# coreboardV0_1sch.net
KiCad netlist of a schematic drawn in Altium Designer
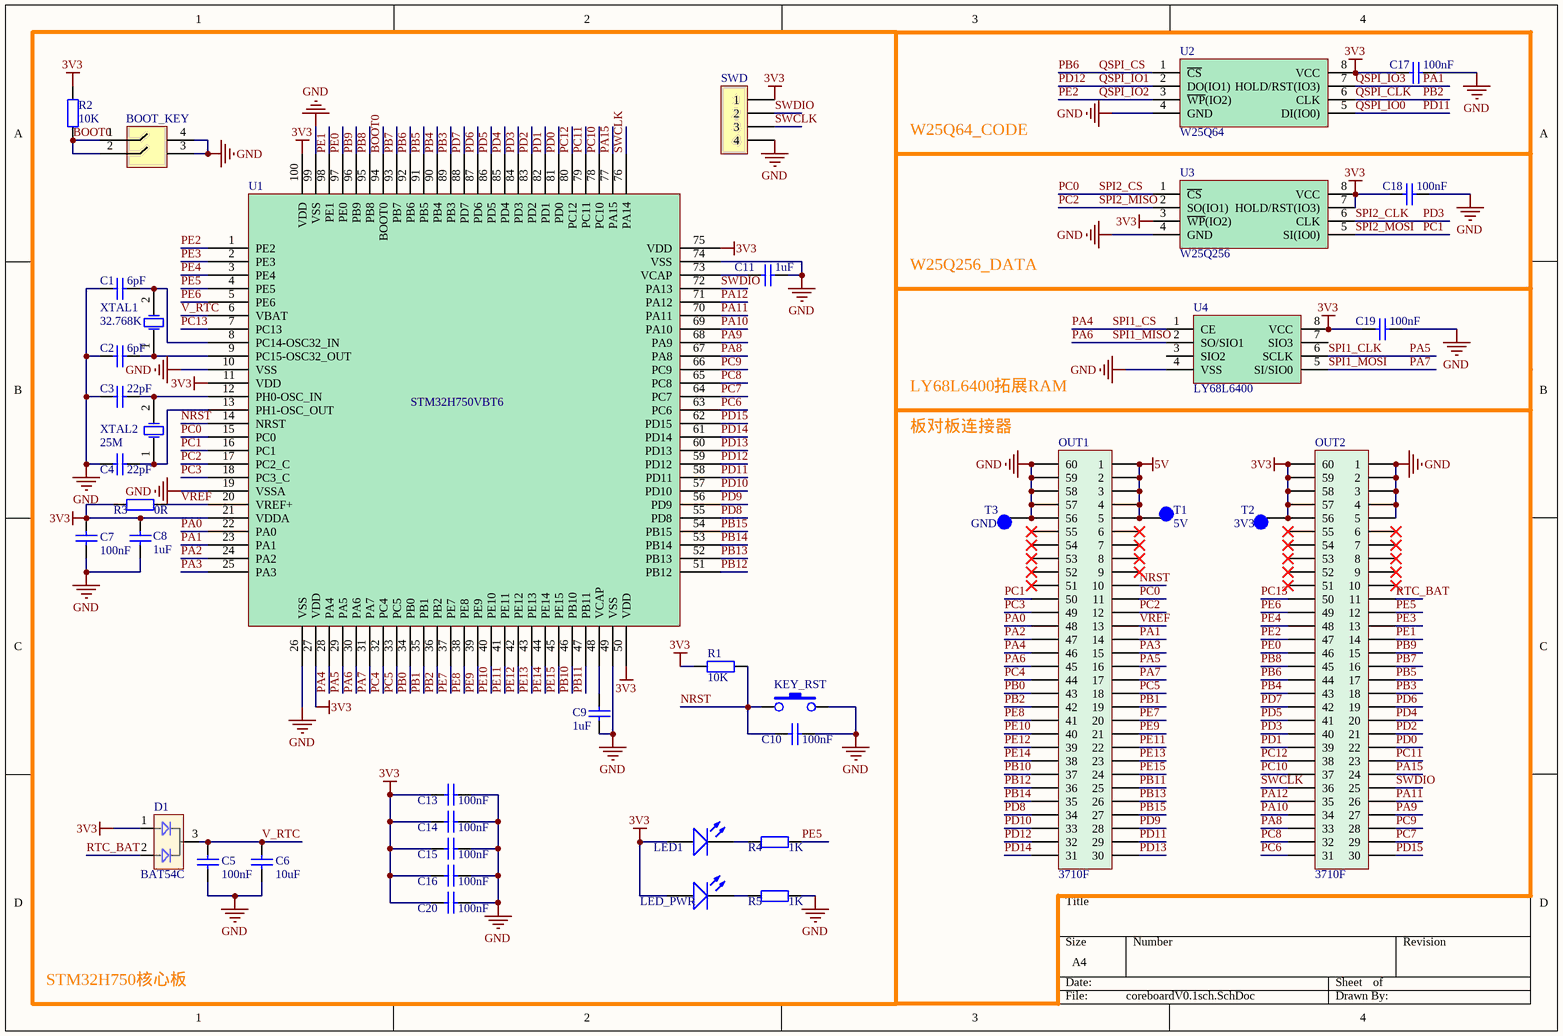
[diagram p0: coreboardV0.1sch.SchDoc]

(export (version "E")
  (design (tool "Eeschema 10.0.6"))
  (components
    (comp (ref "BOOT_KEY")
      (value "KE_2")
      (footprint "KE_2_1.27")
      (libsource (lib "MT_Device") (part "KE_2_1.27"))
    )
    (comp (ref "C1") (value "6pF") (footprint "0603_C") (libsource (lib "MT_Device") (part "0603_CAP")))
    (comp (ref "C2") (value "6pF") (footprint "0603_C") (libsource (lib "MT_Device") (part "0603_CAP")))
    (comp (ref "C3") (value "22pF") (footprint "0603_C") (libsource (lib "MT_Device") (part "0603_CAP")))
    (comp (ref "C4") (value "22pF") (footprint "0603_C") (libsource (lib "MT_Device") (part "0603_CAP")))
    (comp (ref "C5") (value "100nF") (footprint "0603_C") (libsource (lib "MT_Device") (part "0603_CAP")))
    (comp (ref "C6") (value "10uF") (footprint "0603_C") (libsource (lib "MT_Device") (part "0603_CAP")))
    (comp (ref "C7") (value "100nF") (footprint "0603_C") (libsource (lib "MT_Device") (part "0603_CAP")))
    (comp (ref "C8") (value "1uF") (footprint "0603_C") (libsource (lib "MT_Device") (part "0603_CAP")))
    (comp (ref "C9") (value "1uF") (footprint "0603_C") (libsource (lib "MT_Device") (part "0603_CAP")))
    (comp (ref "C10") (value "100nF") (footprint "0603_C") (libsource (lib "MT_Device") (part "0603_CAP")))
    (comp (ref "C11") (value "1uF") (footprint "0603_C") (libsource (lib "MT_Device") (part "0603_CAP")))
    (comp (ref "C13") (value "100nF") (footprint "0603_C") (libsource (lib "MT_Device") (part "0603_CAP")))
    (comp (ref "C14") (value "100nF") (footprint "0603_C") (libsource (lib "MT_Device") (part "0603_CAP")))
    (comp (ref "C15") (value "100nF") (footprint "0603_C") (libsource (lib "MT_Device") (part "0603_CAP")))
    (comp (ref "C16") (value "100nF") (footprint "0603_C") (libsource (lib "MT_Device") (part "0603_CAP")))
    (comp (ref "C17") (value "100nF") (footprint "0603_C") (libsource (lib "MT_Device") (part "0603_CAP")))
    (comp (ref "C18") (value "100nF") (footprint "0603_C") (libsource (lib "MT_Device") (part "0603_CAP")))
    (comp (ref "C19") (value "100nF") (footprint "0603_C") (libsource (lib "MT_Device") (part "0603_CAP")))
    (comp (ref "C20") (value "100nF") (footprint "0603_C") (libsource (lib "MT_Device") (part "0603_CAP")))
    (comp (ref "D1") (value "BAT54C") (footprint "BAT54C") (libsource (lib "MT_Device") (part "BAT54C")))
    (comp (ref "KEY_RST")
      (value "KEY_SMT")
      (footprint "KEY_SMT")
      (libsource (lib "MT_Device") (part "KEY_SMT"))
    )
    (comp (ref "LED1")
      (value "0805_LED")
      (footprint "0805_LED")
      (libsource (lib "MT_Device") (part "0805_LED"))
    )
    (comp (ref "LED_PWR")
      (value "0805_LED")
      (footprint "0805_LED")
      (libsource (lib "MT_Device") (part "0805_LED"))
    )
    (comp (ref "OUT1")
      (value "3710F")
      (footprint "3710F060046G3FT01")
      (libsource (lib "MT_Connector") (part "3710F_30*2pin"))
    )
    (comp (ref "OUT2")
      (value "3710F")
      (footprint "3710F060046G3FT01")
      (libsource (lib "MT_Connector") (part "3710F_30*2pin"))
    )
    (comp (ref "R1") (value "10K") (footprint "0603_R") (libsource (lib "") (part "0603_RES_1")))
    (comp (ref "R2") (value "10K") (footprint "0603_R") (libsource (lib "MT_Device") (part "0603_RES")))
    (comp (ref "R3") (value "0R") (footprint "0603_R") (libsource (lib "") (part "0603_RES_2")))
    (comp (ref "R4") (value "1K") (footprint "0603_R") (libsource (lib "") (part "0603_RES_2")))
    (comp (ref "R5") (value "1K") (footprint "0603_R") (libsource (lib "") (part "0603_RES_2")))
    (comp (ref "SWD")
      (value "Header_2.54_4P")
      (footprint "HDR1_4P")
      (libsource (lib "MT_Connector") (part "Header_2.54_4P"))
    )
    (comp (ref "T1")
      (value "5V")
      (footprint "TEST_POINT_2mm")
      (libsource (lib "MT_Connector") (part "TEST_POINT_2mm"))
    )
    (comp (ref "T2")
      (value "3V3")
      (footprint "TEST_POINT_2mm")
      (libsource (lib "MT_Connector") (part "TEST_POINT_2mm"))
    )
    (comp (ref "T3")
      (value "GND")
      (footprint "TEST_POINT_2mm")
      (libsource (lib "MT_Connector") (part "TEST_POINT_2mm"))
    )
    (comp (ref "U1")
      (value "STM32H750VBT6")
      (footprint "LQFP100")
      (libsource (lib "MT_Chip") (part "STM32H750VBT6"))
    )
    (comp (ref "U2") (value "W25Q64") (footprint "SOIC8-208MIL") (libsource (lib "MT_Chip") (part "W25Q64")))
    (comp (ref "U3") (value "W25Q256") (footprint "WSON8") (libsource (lib "MT_Chip") (part "W25Q256")))
    (comp (ref "U4")
      (value "LY68L6400")
      (footprint "SOP8-150MIL")
      (libsource (lib "MT_Chip") (part "LY68L6400"))
    )
    (comp (ref "XTAL1")
      (value "32.768K")
      (footprint "XTAL_32.768_3215_2")
      (libsource (lib "MT_Device") (part "XTAL_32.768_3215_2"))
    )
    (comp (ref "XTAL2")
      (value "25M")
      (footprint "XTAL_5032_2")
      (libsource (lib "MT_Device") (part "XTAL_8MHz_5032_2"))
    )
  )
  (nets
    (net (code "1") (name "/BOOT0") (class "Default")
      (node (ref "BOOT_KEY") (pin "1") (pinfunction "1_1") (pintype "passive"))
      (node (ref "BOOT_KEY") (pin "2") (pinfunction "2_2") (pintype "passive"))
      (node (ref "R2") (pin "2") (pinfunction "2_2") (pintype "passive"))
      (node (ref "U1") (pin "94") (pinfunction "BOOT0_94") (pintype "passive"))
    )
    (net (code "2") (name "/NRST") (class "Default")
      (node (ref "C10") (pin "2") (pinfunction "2_2") (pintype "passive"))
      (node (ref "KEY_RST") (pin "1") (pinfunction "1_1") (pintype "passive"))
      (node (ref "OUT1") (pin "10") (pinfunction "10_10") (pintype "passive"))
      (node (ref "R1") (pin "1") (pinfunction "1_1") (pintype "passive"))
      (node (ref "U1") (pin "14") (pinfunction "NRST_14") (pintype "passive"))
    )
    (net (code "3") (name "/PA0") (class "Default")
      (node (ref "OUT1") (pin "48") (pinfunction "48_48") (pintype "passive"))
      (node (ref "U1") (pin "22") (pinfunction "PA0_22") (pintype "passive"))
    )
    (net (code "4") (name "/PA1") (class "Default")
      (node (ref "OUT1") (pin "14") (pinfunction "14_14") (pintype "passive"))
      (node (ref "U1") (pin "23") (pinfunction "PA1_23") (pintype "passive"))
      (node (ref "U2") (pin "7") (pinfunction "HOLD/RST(IO3)_7") (pintype "power_in"))
    )
    (net (code "5") (name "/PA2") (class "Default")
      (node (ref "OUT1") (pin "47") (pinfunction "47_47") (pintype "passive"))
      (node (ref "U1") (pin "24") (pinfunction "PA2_24") (pintype "passive"))
    )
    (net (code "6") (name "/PA3") (class "Default")
      (node (ref "OUT1") (pin "15") (pinfunction "15_15") (pintype "passive"))
      (node (ref "U1") (pin "25") (pinfunction "PA3_25") (pintype "passive"))
    )
    (net (code "7") (name "/PA4") (class "Default")
      (node (ref "OUT1") (pin "46") (pinfunction "46_46") (pintype "passive"))
      (node (ref "U1") (pin "28") (pinfunction "PA4_28") (pintype "passive"))
      (node (ref "U4") (pin "1") (pinfunction "CE_1") (pintype "passive"))
    )
    (net (code "8") (name "/PA5") (class "Default")
      (node (ref "OUT1") (pin "16") (pinfunction "16_16") (pintype "passive"))
      (node (ref "U1") (pin "29") (pinfunction "PA5_29") (pintype "passive"))
      (node (ref "U4") (pin "6") (pinfunction "SCLK_6") (pintype "passive"))
    )
    (net (code "9") (name "/PA6") (class "Default")
      (node (ref "OUT1") (pin "45") (pinfunction "45_45") (pintype "passive"))
      (node (ref "U1") (pin "30") (pinfunction "PA6_30") (pintype "passive"))
      (node (ref "U4") (pin "2") (pinfunction "SO/SIO1_2") (pintype "passive"))
    )
    (net (code "10") (name "/PA7") (class "Default")
      (node (ref "OUT1") (pin "17") (pinfunction "17_17") (pintype "passive"))
      (node (ref "U1") (pin "31") (pinfunction "PA7_31") (pintype "passive"))
      (node (ref "U4") (pin "5") (pinfunction "SI/SIO0_5") (pintype "passive"))
    )
    (net (code "11") (name "/PA8") (class "Default")
      (node (ref "OUT2") (pin "33") (pinfunction "33_33") (pintype "passive"))
      (node (ref "U1") (pin "67") (pinfunction "PA8_67") (pintype "passive"))
    )
    (net (code "12") (name "/PA9") (class "Default")
      (node (ref "OUT2") (pin "27") (pinfunction "27_27") (pintype "passive"))
      (node (ref "U1") (pin "68") (pinfunction "PA9_68") (pintype "passive"))
    )
    (net (code "13") (name "/PA10") (class "Default")
      (node (ref "OUT2") (pin "34") (pinfunction "34_34") (pintype "passive"))
      (node (ref "U1") (pin "69") (pinfunction "PA10_69") (pintype "passive"))
    )
    (net (code "14") (name "/PA11") (class "Default")
      (node (ref "OUT2") (pin "26") (pinfunction "26_26") (pintype "passive"))
      (node (ref "U1") (pin "70") (pinfunction "PA11_70") (pintype "passive"))
    )
    (net (code "15") (name "/PA12") (class "Default")
      (node (ref "OUT2") (pin "35") (pinfunction "35_35") (pintype "passive"))
      (node (ref "U1") (pin "71") (pinfunction "PA12_71") (pintype "passive"))
    )
    (net (code "16") (name "/PA15") (class "Default")
      (node (ref "OUT2") (pin "24") (pinfunction "24_24") (pintype "passive"))
      (node (ref "U1") (pin "77") (pinfunction "PA15_77") (pintype "passive"))
    )
    (net (code "17") (name "/PB0") (class "Default")
      (node (ref "OUT1") (pin "43") (pinfunction "43_43") (pintype "passive"))
      (node (ref "U1") (pin "34") (pinfunction "PB0_34") (pintype "passive"))
    )
    (net (code "18") (name "/PB1") (class "Default")
      (node (ref "OUT1") (pin "19") (pinfunction "19_19") (pintype "passive"))
      (node (ref "U1") (pin "35") (pinfunction "PB1_35") (pintype "passive"))
    )
    (net (code "19") (name "/PB2") (class "Default")
      (node (ref "OUT1") (pin "42") (pinfunction "42_42") (pintype "passive"))
      (node (ref "U1") (pin "36") (pinfunction "PB2_36") (pintype "passive"))
      (node (ref "U2") (pin "6") (pinfunction "CLK_6") (pintype "passive"))
    )
    (net (code "20") (name "/PB3") (class "Default")
      (node (ref "OUT2") (pin "18") (pinfunction "18_18") (pintype "passive"))
      (node (ref "U1") (pin "89") (pinfunction "PB3_89") (pintype "passive"))
    )
    (net (code "21") (name "/PB4") (class "Default")
      (node (ref "OUT2") (pin "43") (pinfunction "43_43") (pintype "passive"))
      (node (ref "U1") (pin "90") (pinfunction "PB4_90") (pintype "passive"))
    )
    (net (code "22") (name "/PB5") (class "Default")
      (node (ref "OUT2") (pin "17") (pinfunction "17_17") (pintype "passive"))
      (node (ref "U1") (pin "91") (pinfunction "PB5_91") (pintype "passive"))
    )
    (net (code "23") (name "/PB6") (class "Default")
      (node (ref "OUT2") (pin "44") (pinfunction "44_44") (pintype "passive"))
      (node (ref "U1") (pin "92") (pinfunction "PB6_92") (pintype "passive"))
      (node (ref "U2") (pin "1") (pinfunction "~{CS}_1") (pintype "passive"))
    )
    (net (code "24") (name "/PB7") (class "Default")
      (node (ref "OUT2") (pin "16") (pinfunction "16_16") (pintype "passive"))
      (node (ref "U1") (pin "93") (pinfunction "PB7_93") (pintype "passive"))
    )
    (net (code "25") (name "/PB8") (class "Default")
      (node (ref "OUT2") (pin "45") (pinfunction "45_45") (pintype "passive"))
      (node (ref "U1") (pin "95") (pinfunction "PB8_95") (pintype "passive"))
    )
    (net (code "26") (name "/PB9") (class "Default")
      (node (ref "OUT2") (pin "15") (pinfunction "15_15") (pintype "passive"))
      (node (ref "U1") (pin "96") (pinfunction "PB9_96") (pintype "passive"))
    )
    (net (code "27") (name "/PB10") (class "Default")
      (node (ref "OUT1") (pin "37") (pinfunction "37_37") (pintype "passive"))
      (node (ref "U1") (pin "46") (pinfunction "PB10_46") (pintype "passive"))
    )
    (net (code "28") (name "/PB11") (class "Default")
      (node (ref "OUT1") (pin "25") (pinfunction "25_25") (pintype "passive"))
      (node (ref "U1") (pin "47") (pinfunction "PB11_47") (pintype "passive"))
    )
    (net (code "29") (name "/PB12") (class "Default")
      (node (ref "OUT1") (pin "36") (pinfunction "36_36") (pintype "passive"))
      (node (ref "U1") (pin "51") (pinfunction "PB12_51") (pintype "passive"))
    )
    (net (code "30") (name "/PB13") (class "Default")
      (node (ref "OUT1") (pin "26") (pinfunction "26_26") (pintype "passive"))
      (node (ref "U1") (pin "52") (pinfunction "PB13_52") (pintype "passive"))
    )
    (net (code "31") (name "/PB14") (class "Default")
      (node (ref "OUT1") (pin "35") (pinfunction "35_35") (pintype "passive"))
      (node (ref "U1") (pin "53") (pinfunction "PB14_53") (pintype "passive"))
    )
    (net (code "32") (name "/PB15") (class "Default")
      (node (ref "OUT1") (pin "27") (pinfunction "27_27") (pintype "passive"))
      (node (ref "U1") (pin "54") (pinfunction "PB15_54") (pintype "passive"))
    )
    (net (code "33") (name "/PC0") (class "Default")
      (node (ref "OUT1") (pin "11") (pinfunction "11_11") (pintype "passive"))
      (node (ref "U1") (pin "15") (pinfunction "PC0_15") (pintype "passive"))
      (node (ref "U3") (pin "1") (pinfunction "~{CS}_1") (pintype "passive"))
    )
    (net (code "34") (name "/PC1") (class "Default")
      (node (ref "OUT1") (pin "50") (pinfunction "50_50") (pintype "passive"))
      (node (ref "U1") (pin "16") (pinfunction "PC1_16") (pintype "passive"))
      (node (ref "U3") (pin "5") (pinfunction "SI(IO0)_5") (pintype "power_in"))
    )
    (net (code "35") (name "/PC2") (class "Default")
      (node (ref "OUT1") (pin "12") (pinfunction "12_12") (pintype "passive"))
      (node (ref "U1") (pin "17") (pinfunction "PC2_C_17") (pintype "passive"))
      (node (ref "U3") (pin "2") (pinfunction "SO(IO1)_2") (pintype "passive"))
    )
    (net (code "36") (name "/PC3") (class "Default")
      (node (ref "OUT1") (pin "49") (pinfunction "49_49") (pintype "passive"))
      (node (ref "U1") (pin "18") (pinfunction "PC3_C_18") (pintype "passive"))
    )
    (net (code "37") (name "/PC4") (class "Default")
      (node (ref "OUT1") (pin "44") (pinfunction "44_44") (pintype "passive"))
      (node (ref "U1") (pin "32") (pinfunction "PC4_32") (pintype "passive"))
    )
    (net (code "38") (name "/PC5") (class "Default")
      (node (ref "OUT1") (pin "18") (pinfunction "18_18") (pintype "passive"))
      (node (ref "U1") (pin "33") (pinfunction "PC5_33") (pintype "passive"))
    )
    (net (code "39") (name "/PC6") (class "Default")
      (node (ref "OUT2") (pin "31") (pinfunction "31_31") (pintype "passive"))
      (node (ref "U1") (pin "63") (pinfunction "PC6_63") (pintype "passive"))
    )
    (net (code "40") (name "/PC7") (class "Default")
      (node (ref "OUT2") (pin "29") (pinfunction "29_29") (pintype "passive"))
      (node (ref "U1") (pin "64") (pinfunction "PC7_64") (pintype "passive"))
    )
    (net (code "41") (name "/PC8") (class "Default")
      (node (ref "OUT2") (pin "32") (pinfunction "32_32") (pintype "passive"))
      (node (ref "U1") (pin "65") (pinfunction "PC8_65") (pintype "passive"))
    )
    (net (code "42") (name "/PC9") (class "Default")
      (node (ref "OUT2") (pin "28") (pinfunction "28_28") (pintype "passive"))
      (node (ref "U1") (pin "66") (pinfunction "PC9_66") (pintype "passive"))
    )
    (net (code "43") (name "/PC10") (class "Default")
      (node (ref "OUT2") (pin "37") (pinfunction "37_37") (pintype "passive"))
      (node (ref "U1") (pin "78") (pinfunction "PC10_78") (pintype "passive"))
    )
    (net (code "44") (name "/PC11") (class "Default")
      (node (ref "OUT2") (pin "23") (pinfunction "23_23") (pintype "passive"))
      (node (ref "U1") (pin "79") (pinfunction "PC11_79") (pintype "passive"))
    )
    (net (code "45") (name "/PC12") (class "Default")
      (node (ref "OUT2") (pin "38") (pinfunction "38_38") (pintype "passive"))
      (node (ref "U1") (pin "80") (pinfunction "PC12_80") (pintype "passive"))
    )
    (net (code "46") (name "/PC13") (class "Default")
      (node (ref "OUT2") (pin "50") (pinfunction "50_50") (pintype "passive"))
      (node (ref "U1") (pin "7") (pinfunction "PC13_7") (pintype "passive"))
    )
    (net (code "47") (name "/PD0") (class "Default")
      (node (ref "OUT2") (pin "22") (pinfunction "22_22") (pintype "passive"))
      (node (ref "U1") (pin "81") (pinfunction "PD0_81") (pintype "passive"))
    )
    (net (code "48") (name "/PD1") (class "Default")
      (node (ref "OUT2") (pin "39") (pinfunction "39_39") (pintype "passive"))
      (node (ref "U1") (pin "82") (pinfunction "PD1_82") (pintype "passive"))
    )
    (net (code "49") (name "/PD2") (class "Default")
      (node (ref "OUT2") (pin "21") (pinfunction "21_21") (pintype "passive"))
      (node (ref "U1") (pin "83") (pinfunction "PD2_83") (pintype "passive"))
    )
    (net (code "50") (name "/PD3") (class "Default")
      (node (ref "OUT2") (pin "40") (pinfunction "40_40") (pintype "passive"))
      (node (ref "U1") (pin "84") (pinfunction "PD3_84") (pintype "passive"))
      (node (ref "U3") (pin "6") (pinfunction "CLK_6") (pintype "passive"))
    )
    (net (code "51") (name "/PD4") (class "Default")
      (node (ref "OUT2") (pin "20") (pinfunction "20_20") (pintype "passive"))
      (node (ref "U1") (pin "85") (pinfunction "PD4_85") (pintype "passive"))
    )
    (net (code "52") (name "/PD5") (class "Default")
      (node (ref "OUT2") (pin "41") (pinfunction "41_41") (pintype "passive"))
      (node (ref "U1") (pin "86") (pinfunction "PD5_86") (pintype "passive"))
    )
    (net (code "53") (name "/PD6") (class "Default")
      (node (ref "OUT2") (pin "19") (pinfunction "19_19") (pintype "passive"))
      (node (ref "U1") (pin "87") (pinfunction "PD6_87") (pintype "passive"))
    )
    (net (code "54") (name "/PD7") (class "Default")
      (node (ref "OUT2") (pin "42") (pinfunction "42_42") (pintype "passive"))
      (node (ref "U1") (pin "88") (pinfunction "PD7_88") (pintype "passive"))
    )
    (net (code "55") (name "/PD8") (class "Default")
      (node (ref "OUT1") (pin "34") (pinfunction "34_34") (pintype "passive"))
      (node (ref "U1") (pin "55") (pinfunction "PD8_55") (pintype "passive"))
    )
    (net (code "56") (name "/PD9") (class "Default")
      (node (ref "OUT1") (pin "28") (pinfunction "28_28") (pintype "passive"))
      (node (ref "U1") (pin "56") (pinfunction "PD9_56") (pintype "passive"))
    )
    (net (code "57") (name "/PD10") (class "Default")
      (node (ref "OUT1") (pin "33") (pinfunction "33_33") (pintype "passive"))
      (node (ref "U1") (pin "57") (pinfunction "PD10_57") (pintype "passive"))
    )
    (net (code "58") (name "/PD11") (class "Default")
      (node (ref "OUT1") (pin "29") (pinfunction "29_29") (pintype "passive"))
      (node (ref "U1") (pin "58") (pinfunction "PD11_58") (pintype "passive"))
      (node (ref "U2") (pin "5") (pinfunction "DI(IO0)_5") (pintype "power_in"))
    )
    (net (code "59") (name "/PD12") (class "Default")
      (node (ref "OUT1") (pin "32") (pinfunction "32_32") (pintype "passive"))
      (node (ref "U1") (pin "59") (pinfunction "PD12_59") (pintype "passive"))
      (node (ref "U2") (pin "2") (pinfunction "DO(IO1)_2") (pintype "passive"))
    )
    (net (code "60") (name "/PD13") (class "Default")
      (node (ref "OUT1") (pin "30") (pinfunction "30_30") (pintype "passive"))
      (node (ref "U1") (pin "60") (pinfunction "PD13_60") (pintype "passive"))
    )
    (net (code "61") (name "/PD14") (class "Default")
      (node (ref "OUT1") (pin "31") (pinfunction "31_31") (pintype "passive"))
      (node (ref "U1") (pin "61") (pinfunction "PD14_61") (pintype "passive"))
    )
    (net (code "62") (name "/PD15") (class "Default")
      (node (ref "OUT2") (pin "30") (pinfunction "30_30") (pintype "passive"))
      (node (ref "U1") (pin "62") (pinfunction "PD15_62") (pintype "passive"))
    )
    (net (code "63") (name "/PE0") (class "Default")
      (node (ref "OUT2") (pin "46") (pinfunction "46_46") (pintype "passive"))
      (node (ref "U1") (pin "97") (pinfunction "PE0_97") (pintype "passive"))
    )
    (net (code "64") (name "/PE1") (class "Default")
      (node (ref "OUT2") (pin "14") (pinfunction "14_14") (pintype "passive"))
      (node (ref "U1") (pin "98") (pinfunction "PE1_98") (pintype "passive"))
    )
    (net (code "65") (name "/PE2") (class "Default")
      (node (ref "OUT2") (pin "47") (pinfunction "47_47") (pintype "passive"))
      (node (ref "U1") (pin "1") (pinfunction "PE2_1") (pintype "passive"))
      (node (ref "U2") (pin "3") (pinfunction "~{WP}(IO2)_3") (pintype "passive"))
    )
    (net (code "66") (name "/PE3") (class "Default")
      (node (ref "OUT2") (pin "13") (pinfunction "13_13") (pintype "passive"))
      (node (ref "U1") (pin "2") (pinfunction "PE3_2") (pintype "passive"))
    )
    (net (code "67") (name "/PE4") (class "Default")
      (node (ref "OUT2") (pin "48") (pinfunction "48_48") (pintype "passive"))
      (node (ref "U1") (pin "3") (pinfunction "PE4_3") (pintype "passive"))
    )
    (net (code "68") (name "/PE5") (class "Default")
      (node (ref "OUT2") (pin "12") (pinfunction "12_12") (pintype "passive"))
      (node (ref "R4") (pin "2") (pinfunction "2_2") (pintype "passive"))
      (node (ref "U1") (pin "4") (pinfunction "PE5_4") (pintype "passive"))
    )
    (net (code "69") (name "/PE6") (class "Default")
      (node (ref "OUT2") (pin "49") (pinfunction "49_49") (pintype "passive"))
      (node (ref "U1") (pin "5") (pinfunction "PE6_5") (pintype "passive"))
    )
    (net (code "70") (name "/PE7") (class "Default")
      (node (ref "OUT1") (pin "20") (pinfunction "20_20") (pintype "passive"))
      (node (ref "U1") (pin "37") (pinfunction "PE7_37") (pintype "passive"))
    )
    (net (code "71") (name "/PE8") (class "Default")
      (node (ref "OUT1") (pin "41") (pinfunction "41_41") (pintype "passive"))
      (node (ref "U1") (pin "38") (pinfunction "PE8_38") (pintype "passive"))
    )
    (net (code "72") (name "/PE9") (class "Default")
      (node (ref "OUT1") (pin "21") (pinfunction "21_21") (pintype "passive"))
      (node (ref "U1") (pin "39") (pinfunction "PE9_39") (pintype "passive"))
    )
    (net (code "73") (name "/PE10") (class "Default")
      (node (ref "OUT1") (pin "40") (pinfunction "40_40") (pintype "passive"))
      (node (ref "U1") (pin "40") (pinfunction "PE10_40") (pintype "passive"))
    )
    (net (code "74") (name "/PE11") (class "Default")
      (node (ref "OUT1") (pin "22") (pinfunction "22_22") (pintype "passive"))
      (node (ref "U1") (pin "41") (pinfunction "PE11_41") (pintype "passive"))
    )
    (net (code "75") (name "/PE12") (class "Default")
      (node (ref "OUT1") (pin "39") (pinfunction "39_39") (pintype "passive"))
      (node (ref "U1") (pin "42") (pinfunction "PE12_42") (pintype "passive"))
    )
    (net (code "76") (name "/PE13") (class "Default")
      (node (ref "OUT1") (pin "23") (pinfunction "23_23") (pintype "passive"))
      (node (ref "U1") (pin "43") (pinfunction "PE13_43") (pintype "passive"))
    )
    (net (code "77") (name "/PE14") (class "Default")
      (node (ref "OUT1") (pin "38") (pinfunction "38_38") (pintype "passive"))
      (node (ref "U1") (pin "44") (pinfunction "PE14_44") (pintype "passive"))
    )
    (net (code "78") (name "/PE15") (class "Default")
      (node (ref "OUT1") (pin "24") (pinfunction "24_24") (pintype "passive"))
      (node (ref "U1") (pin "45") (pinfunction "PE15_45") (pintype "passive"))
    )
    (net (code "79") (name "/RTC_BAT") (class "Default")
      (node (ref "D1") (pin "2") (pinfunction "2_2") (pintype "passive"))
      (node (ref "OUT2") (pin "11") (pinfunction "11_11") (pintype "passive"))
    )
    (net (code "80") (name "/SWCLK") (class "Default")
      (node (ref "OUT2") (pin "36") (pinfunction "36_36") (pintype "passive"))
      (node (ref "SWD") (pin "3") (pinfunction "3_3") (pintype "passive"))
      (node (ref "U1") (pin "76") (pinfunction "PA14_76") (pintype "passive"))
    )
    (net (code "81") (name "/SWDIO") (class "Default")
      (node (ref "OUT2") (pin "25") (pinfunction "25_25") (pintype "passive"))
      (node (ref "SWD") (pin "2") (pinfunction "2_2") (pintype "passive"))
      (node (ref "U1") (pin "72") (pinfunction "PA13_72") (pintype "passive"))
    )
    (net (code "82") (name "/VREF") (class "Default")
      (node (ref "OUT1") (pin "13") (pinfunction "13_13") (pintype "passive"))
      (node (ref "R3") (pin "2") (pinfunction "2_2") (pintype "passive"))
      (node (ref "U1") (pin "20") (pinfunction "VREF+_20") (pintype "passive"))
    )
    (net (code "83") (name "/V_RTC") (class "Default")
      (node (ref "C5") (pin "2") (pinfunction "2_2") (pintype "passive"))
      (node (ref "C6") (pin "2") (pinfunction "2_2") (pintype "passive"))
      (node (ref "D1") (pin "3") (pinfunction "3_3") (pintype "passive"))
      (node (ref "U1") (pin "6") (pinfunction "VBAT_6") (pintype "passive"))
    )
    (net (code "84") (name "3V3") (class "Default")
      (node (ref "C13") (pin "2") (pinfunction "2_2") (pintype "passive"))
      (node (ref "C14") (pin "2") (pinfunction "2_2") (pintype "passive"))
      (node (ref "C15") (pin "2") (pinfunction "2_2") (pintype "passive"))
      (node (ref "C16") (pin "2") (pinfunction "2_2") (pintype "passive"))
      (node (ref "C17") (pin "1") (pinfunction "1_1") (pintype "passive"))
      (node (ref "C18") (pin "1") (pinfunction "1_1") (pintype "passive"))
      (node (ref "C19") (pin "1") (pinfunction "1_1") (pintype "passive"))
      (node (ref "C20") (pin "2") (pinfunction "2_2") (pintype "passive"))
      (node (ref "C7") (pin "2") (pinfunction "2_2") (pintype "passive"))
      (node (ref "C8") (pin "1") (pinfunction "1_1") (pintype "passive"))
      (node (ref "D1") (pin "1") (pinfunction "1_1") (pintype "passive"))
      (node (ref "LED1") (pin "A") (pinfunction "A_A") (pintype "passive"))
      (node (ref "LED_PWR") (pin "A") (pinfunction "A_A") (pintype "passive"))
      (node (ref "OUT2") (pin "56") (pinfunction "56_56") (pintype "passive"))
      (node (ref "OUT2") (pin "57") (pinfunction "57_57") (pintype "passive"))
      (node (ref "OUT2") (pin "58") (pinfunction "58_58") (pintype "passive"))
      (node (ref "OUT2") (pin "59") (pinfunction "59_59") (pintype "passive"))
      (node (ref "OUT2") (pin "60") (pinfunction "60_60") (pintype "passive"))
      (node (ref "R1") (pin "2") (pinfunction "2_2") (pintype "passive"))
      (node (ref "R2") (pin "1") (pinfunction "1_1") (pintype "passive"))
      (node (ref "R3") (pin "1") (pinfunction "1_1") (pintype "passive"))
      (node (ref "SWD") (pin "1") (pinfunction "1_1") (pintype "passive"))
      (node (ref "T2") (pin "1") (pinfunction "1_1") (pintype "passive"))
      (node (ref "U1") (pin "100") (pinfunction "VDD_100") (pintype "passive"))
      (node (ref "U1") (pin "11") (pinfunction "VDD_11") (pintype "passive"))
      (node (ref "U1") (pin "21") (pinfunction "VDDA_21") (pintype "passive"))
      (node (ref "U1") (pin "27") (pinfunction "VDD_27") (pintype "passive"))
      (node (ref "U1") (pin "50") (pinfunction "VDD_50") (pintype "passive"))
      (node (ref "U1") (pin "75") (pinfunction "VDD_75") (pintype "passive"))
      (node (ref "U2") (pin "8") (pinfunction "VCC_8") (pintype "passive"))
      (node (ref "U3") (pin "3") (pinfunction "~{WP}(IO2)_3") (pintype "passive"))
      (node (ref "U3") (pin "7") (pinfunction "HOLD/RST(IO3)_7") (pintype "power_in"))
      (node (ref "U3") (pin "8") (pinfunction "VCC_8") (pintype "passive"))
      (node (ref "U4") (pin "8") (pinfunction "VCC_8") (pintype "passive"))
    )
    (net (code "85") (name "5V") (class "Default")
      (node (ref "OUT1") (pin "1") (pinfunction "1_1") (pintype "passive"))
      (node (ref "OUT1") (pin "2") (pinfunction "2_2") (pintype "passive"))
      (node (ref "OUT1") (pin "3") (pinfunction "3_3") (pintype "passive"))
      (node (ref "OUT1") (pin "4") (pinfunction "4_4") (pintype "passive"))
      (node (ref "OUT1") (pin "5") (pinfunction "5_5") (pintype "passive"))
      (node (ref "T1") (pin "1") (pinfunction "1_1") (pintype "passive"))
    )
    (net (code "86") (name "GND") (class "Default")
      (node (ref "BOOT_KEY") (pin "3") (pinfunction "3_3") (pintype "passive"))
      (node (ref "BOOT_KEY") (pin "4") (pinfunction "4_4") (pintype "passive"))
      (node (ref "C1") (pin "1") (pinfunction "1_1") (pintype "passive"))
      (node (ref "C10") (pin "1") (pinfunction "1_1") (pintype "passive"))
      (node (ref "C11") (pin "2") (pinfunction "2_2") (pintype "passive"))
      (node (ref "C13") (pin "1") (pinfunction "1_1") (pintype "passive"))
      (node (ref "C14") (pin "1") (pinfunction "1_1") (pintype "passive"))
      (node (ref "C15") (pin "1") (pinfunction "1_1") (pintype "passive"))
      (node (ref "C16") (pin "1") (pinfunction "1_1") (pintype "passive"))
      (node (ref "C17") (pin "2") (pinfunction "2_2") (pintype "passive"))
      (node (ref "C18") (pin "2") (pinfunction "2_2") (pintype "passive"))
      (node (ref "C19") (pin "2") (pinfunction "2_2") (pintype "passive"))
      (node (ref "C2") (pin "1") (pinfunction "1_1") (pintype "passive"))
      (node (ref "C20") (pin "1") (pinfunction "1_1") (pintype "passive"))
      (node (ref "C3") (pin "1") (pinfunction "1_1") (pintype "passive"))
      (node (ref "C4") (pin "1") (pinfunction "1_1") (pintype "passive"))
      (node (ref "C5") (pin "1") (pinfunction "1_1") (pintype "passive"))
      (node (ref "C6") (pin "1") (pinfunction "1_1") (pintype "passive"))
      (node (ref "C7") (pin "1") (pinfunction "1_1") (pintype "passive"))
      (node (ref "C8") (pin "2") (pinfunction "2_2") (pintype "passive"))
      (node (ref "C9") (pin "2") (pinfunction "2_2") (pintype "passive"))
      (node (ref "KEY_RST") (pin "2") (pinfunction "2_2") (pintype "passive"))
      (node (ref "OUT1") (pin "56") (pinfunction "56_56") (pintype "passive"))
      (node (ref "OUT1") (pin "57") (pinfunction "57_57") (pintype "passive"))
      (node (ref "OUT1") (pin "58") (pinfunction "58_58") (pintype "passive"))
      (node (ref "OUT1") (pin "59") (pinfunction "59_59") (pintype "passive"))
      (node (ref "OUT1") (pin "60") (pinfunction "60_60") (pintype "passive"))
      (node (ref "OUT2") (pin "1") (pinfunction "1_1") (pintype "passive"))
      (node (ref "OUT2") (pin "2") (pinfunction "2_2") (pintype "passive"))
      (node (ref "OUT2") (pin "3") (pinfunction "3_3") (pintype "passive"))
      (node (ref "OUT2") (pin "4") (pinfunction "4_4") (pintype "passive"))
      (node (ref "OUT2") (pin "5") (pinfunction "5_5") (pintype "passive"))
      (node (ref "R5") (pin "2") (pinfunction "2_2") (pintype "passive"))
      (node (ref "SWD") (pin "4") (pinfunction "4_4") (pintype "passive"))
      (node (ref "T3") (pin "1") (pinfunction "1_1") (pintype "passive"))
      (node (ref "U1") (pin "10") (pinfunction "VSS_10") (pintype "passive"))
      (node (ref "U1") (pin "19") (pinfunction "VSSA_19") (pintype "passive"))
      (node (ref "U1") (pin "26") (pinfunction "VSS_26") (pintype "passive"))
      (node (ref "U1") (pin "49") (pinfunction "VSS_49") (pintype "passive"))
      (node (ref "U1") (pin "74") (pinfunction "VSS_74") (pintype "passive"))
      (node (ref "U1") (pin "99") (pinfunction "VSS_99") (pintype "passive"))
      (node (ref "U2") (pin "4") (pinfunction "GND_4") (pintype "passive"))
      (node (ref "U3") (pin "4") (pinfunction "GND_4") (pintype "passive"))
      (node (ref "U4") (pin "4") (pinfunction "VSS_4") (pintype "passive"))
    )
    (net (code "87") (name "Net-(C9-Pad1)") (class "Default")
      (node (ref "C9") (pin "1") (pinfunction "1_1") (pintype "passive"))
      (node (ref "U1") (pin "48") (pinfunction "VCAP_48") (pintype "passive"))
    )
    (net (code "88") (name "Net-(C11-Pad1)") (class "Default")
      (node (ref "C11") (pin "1") (pinfunction "1_1") (pintype "passive"))
      (node (ref "U1") (pin "73") (pinfunction "VCAP_73") (pintype "passive"))
    )
    (net (code "89") (name "Net-(LED1-PadK)") (class "Default")
      (node (ref "LED1") (pin "K") (pinfunction "K_K") (pintype "passive"))
      (node (ref "R4") (pin "1") (pinfunction "1_1") (pintype "passive"))
    )
    (net (code "90") (name "Net-(LED_PWR-PadK)") (class "Default")
      (node (ref "LED_PWR") (pin "K") (pinfunction "K_K") (pintype "passive"))
      (node (ref "R5") (pin "1") (pinfunction "1_1") (pintype "passive"))
    )
    (net (code "91") (name "Net-(U1-PC14-OSC32_IN)") (class "Default")
      (node (ref "C1") (pin "2") (pinfunction "2_2") (pintype "passive"))
      (node (ref "U1") (pin "8") (pinfunction "PC14-OSC32_IN_8") (pintype "passive"))
      (node (ref "XTAL1") (pin "2") (pinfunction "OSC2_2") (pintype "passive"))
    )
    (net (code "92") (name "Net-(U1-PC15-OSC32_OUT)") (class "Default")
      (node (ref "C2") (pin "2") (pinfunction "2_2") (pintype "passive"))
      (node (ref "U1") (pin "9") (pinfunction "PC15-OSC32_OUT_9") (pintype "passive"))
      (node (ref "XTAL1") (pin "1") (pinfunction "OSC1_1") (pintype "passive"))
    )
    (net (code "93") (name "Net-(U1-PH0-OSC_IN)") (class "Default")
      (node (ref "C3") (pin "2") (pinfunction "2_2") (pintype "passive"))
      (node (ref "U1") (pin "12") (pinfunction "PH0-OSC_IN_12") (pintype "passive"))
      (node (ref "XTAL2") (pin "2") (pinfunction "OSC2_2") (pintype "passive"))
    )
    (net (code "94") (name "Net-(U1-PH1-OSC_OUT)") (class "Default")
      (node (ref "C4") (pin "2") (pinfunction "2_2") (pintype "passive"))
      (node (ref "U1") (pin "13") (pinfunction "PH1-OSC_OUT_13") (pintype "passive"))
      (node (ref "XTAL2") (pin "1") (pinfunction "OSC1_1") (pintype "passive"))
    )
    (net (code "95") (name "unconnected-(OUT1-Pad6)") (class "Default")
      (node (ref "OUT1") (pin "6") (pinfunction "6_6") (pintype "passive+no_connect"))
    )
    (net (code "96") (name "unconnected-(OUT1-Pad7)") (class "Default")
      (node (ref "OUT1") (pin "7") (pinfunction "7_7") (pintype "passive+no_connect"))
    )
    (net (code "97") (name "unconnected-(OUT1-Pad8)") (class "Default")
      (node (ref "OUT1") (pin "8") (pinfunction "8_8") (pintype "passive+no_connect"))
    )
    (net (code "98") (name "unconnected-(OUT1-Pad9)") (class "Default")
      (node (ref "OUT1") (pin "9") (pinfunction "9_9") (pintype "passive+no_connect"))
    )
    (net (code "99") (name "unconnected-(OUT1-Pad51)") (class "Default")
      (node (ref "OUT1") (pin "51") (pinfunction "51_51") (pintype "passive+no_connect"))
    )
    (net (code "100") (name "unconnected-(OUT1-Pad52)") (class "Default")
      (node (ref "OUT1") (pin "52") (pinfunction "52_52") (pintype "passive+no_connect"))
    )
    (net (code "101") (name "unconnected-(OUT1-Pad53)") (class "Default")
      (node (ref "OUT1") (pin "53") (pinfunction "53_53") (pintype "passive+no_connect"))
    )
    (net (code "102") (name "unconnected-(OUT1-Pad54)") (class "Default")
      (node (ref "OUT1") (pin "54") (pinfunction "54_54") (pintype "passive+no_connect"))
    )
    (net (code "103") (name "unconnected-(OUT1-Pad55)") (class "Default")
      (node (ref "OUT1") (pin "55") (pinfunction "55_55") (pintype "passive+no_connect"))
    )
    (net (code "104") (name "unconnected-(OUT2-Pad6)") (class "Default")
      (node (ref "OUT2") (pin "6") (pinfunction "6_6") (pintype "passive+no_connect"))
    )
    (net (code "105") (name "unconnected-(OUT2-Pad7)") (class "Default")
      (node (ref "OUT2") (pin "7") (pinfunction "7_7") (pintype "passive+no_connect"))
    )
    (net (code "106") (name "unconnected-(OUT2-Pad8)") (class "Default")
      (node (ref "OUT2") (pin "8") (pinfunction "8_8") (pintype "passive+no_connect"))
    )
    (net (code "107") (name "unconnected-(OUT2-Pad9)") (class "Default")
      (node (ref "OUT2") (pin "9") (pinfunction "9_9") (pintype "passive+no_connect"))
    )
    (net (code "108") (name "unconnected-(OUT2-Pad10)") (class "Default")
      (node (ref "OUT2") (pin "10") (pinfunction "10_10") (pintype "passive+no_connect"))
    )
    (net (code "109") (name "unconnected-(OUT2-Pad51)") (class "Default")
      (node (ref "OUT2") (pin "51") (pinfunction "51_51") (pintype "passive+no_connect"))
    )
    (net (code "110") (name "unconnected-(OUT2-Pad52)") (class "Default")
      (node (ref "OUT2") (pin "52") (pinfunction "52_52") (pintype "passive+no_connect"))
    )
    (net (code "111") (name "unconnected-(OUT2-Pad53)") (class "Default")
      (node (ref "OUT2") (pin "53") (pinfunction "53_53") (pintype "passive+no_connect"))
    )
    (net (code "112") (name "unconnected-(OUT2-Pad54)") (class "Default")
      (node (ref "OUT2") (pin "54") (pinfunction "54_54") (pintype "passive+no_connect"))
    )
    (net (code "113") (name "unconnected-(OUT2-Pad55)") (class "Default")
      (node (ref "OUT2") (pin "55") (pinfunction "55_55") (pintype "passive+no_connect"))
    )
    (net (code "114") (name "unconnected-(U4-SIO2-Pad3)") (class "Default")
      (node (ref "U4") (pin "3") (pinfunction "SIO2_3") (pintype "passive"))
    )
    (net (code "115") (name "unconnected-(U4-SIO3-Pad7)") (class "Default")
      (node (ref "U4") (pin "7") (pinfunction "SIO3_7") (pintype "passive"))
    )
  )
)
